# HshNano_v1_0.net
KiCad netlist of a schematic drawn in EAGLE
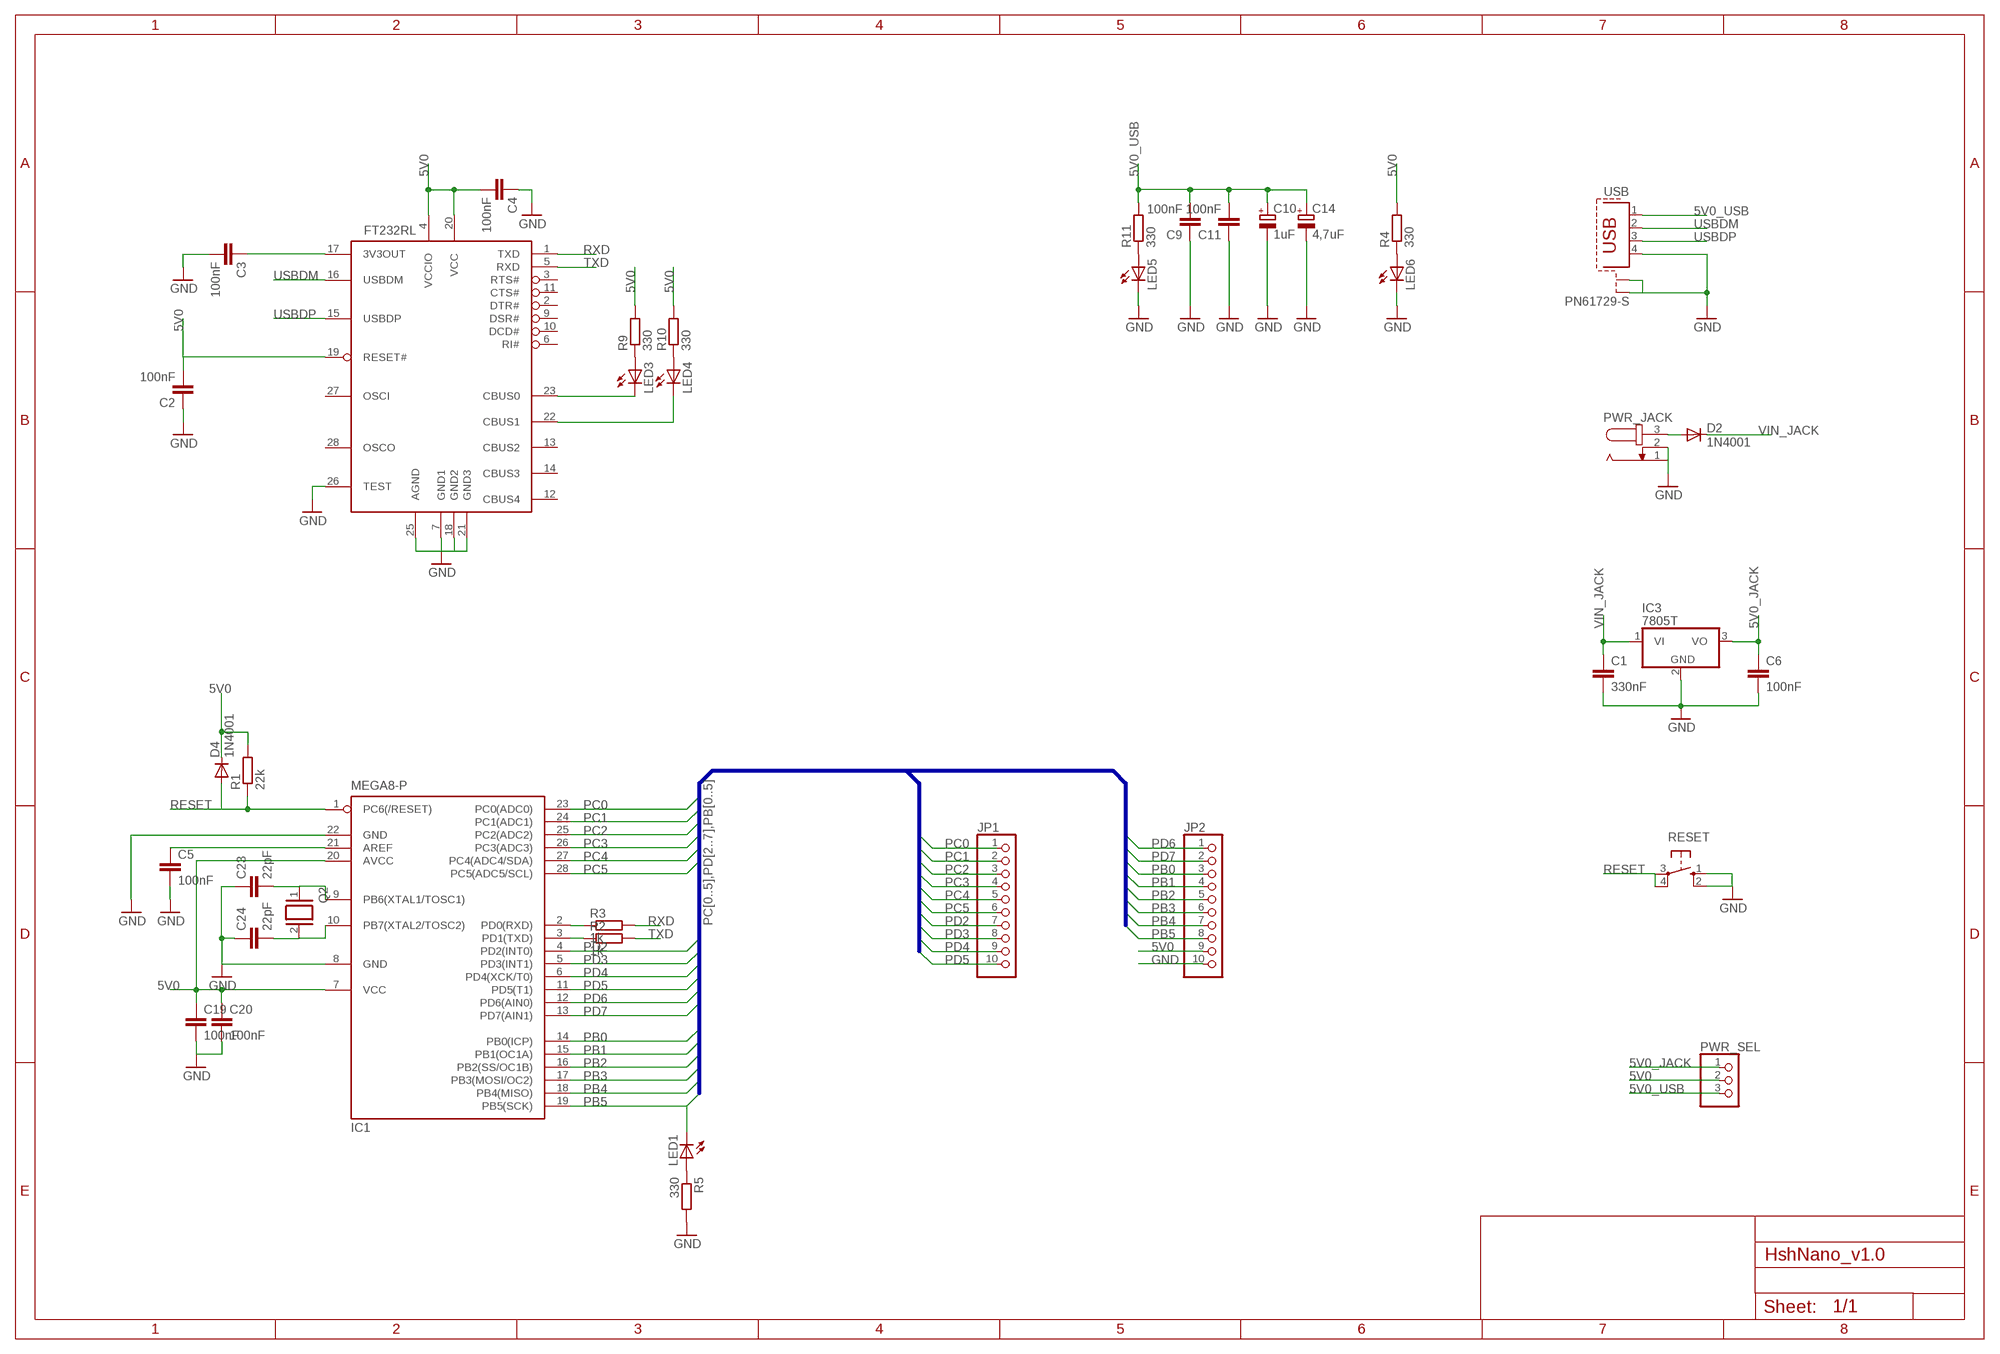
[diagram p0: schematic, sheet 1]

(export (version "E")
  (design (tool "Eeschema 10.0.6"))
  (components
    (comp (ref "C1")
      (value "330nF")
      (footprint "eagle-import:C025-025X050")
      (libsource (lib "eagle-import") (part "C-EU025-025X050"))
    )
    (comp (ref "C2")
      (value "100nF")
      (footprint "eagle-import:C025-025X050")
      (libsource (lib "eagle-import") (part "C-EU025-025X050"))
    )
    (comp (ref "C3")
      (value "100nF")
      (footprint "eagle-import:C025-025X050")
      (libsource (lib "eagle-import") (part "C-EU025-025X050"))
    )
    (comp (ref "C4")
      (value "100nF")
      (footprint "eagle-import:C025-025X050")
      (libsource (lib "eagle-import") (part "C-EU025-025X050"))
    )
    (comp (ref "C5")
      (value "100nF")
      (footprint "eagle-import:C025-025X050")
      (libsource (lib "eagle-import") (part "C-EU025-025X050"))
    )
    (comp (ref "C6")
      (value "100nF")
      (footprint "eagle-import:C025-025X050")
      (libsource (lib "eagle-import") (part "C-EU025-025X050"))
    )
    (comp (ref "C9")
      (value "100nF")
      (footprint "eagle-import:C025-025X050")
      (libsource (lib "eagle-import") (part "C-EU025-025X050"))
    )
    (comp (ref "C10")
      (value "1uF")
      (footprint "eagle-import:E2,5-5")
      (libsource (lib "eagle-import") (part "CPOL-EUE2.5-5"))
    )
    (comp (ref "C11")
      (value "100nF")
      (footprint "eagle-import:C025-025X050")
      (libsource (lib "eagle-import") (part "C-EU025-025X050"))
    )
    (comp (ref "C14")
      (value "4,7uF")
      (footprint "eagle-import:E2,5-5")
      (libsource (lib "eagle-import") (part "CPOL-EUE2.5-5"))
    )
    (comp (ref "C19")
      (value "100nF")
      (footprint "eagle-import:C025-025X050")
      (libsource (lib "eagle-import") (part "C-EU025-025X050"))
    )
    (comp (ref "C20")
      (value "100nF")
      (footprint "eagle-import:C025-025X050")
      (libsource (lib "eagle-import") (part "C-EU025-025X050"))
    )
    (comp (ref "C23")
      (value "22pF")
      (footprint "eagle-import:C025-025X050")
      (libsource (lib "eagle-import") (part "C-EU025-025X050"))
    )
    (comp (ref "C24")
      (value "22pF")
      (footprint "eagle-import:C025-025X050")
      (libsource (lib "eagle-import") (part "C-EU025-025X050"))
    )
    (comp (ref "D2")
      (value "1N4001")
      (footprint "eagle-import:DO41-10")
      (libsource (lib "eagle-import") (part "1N4004"))
    )
    (comp (ref "D4")
      (value "1N4001")
      (footprint "eagle-import:DO41-10")
      (libsource (lib "eagle-import") (part "1N4004"))
    )
    (comp (ref "FT232RL")
      (value "FT232RL")
      (footprint "eagle-import:SSOP28DB")
      (libsource (lib "eagle-import") (part "FT232RL"))
    )
    (comp (ref "IC1")
      (value "MEGA8-P")
      (footprint "eagle-import:DIL28-3")
      (libsource (lib "eagle-import") (part "MEGA8-P"))
    )
    (comp (ref "IC3")
      (value "7805T")
      (footprint "eagle-import:TO220H")
      (libsource (lib "eagle-import") (part "78T05"))
    )
    (comp (ref "JP1")
      (value "PINHD-1X10")
      (footprint "eagle-import:1X10")
      (libsource (lib "eagle-import") (part "PINHD-1X10"))
    )
    (comp (ref "JP2")
      (value "PINHD-1X10")
      (footprint "eagle-import:1X10")
      (libsource (lib "eagle-import") (part "PINHD-1X10"))
    )
    (comp (ref "LED1")
      (value "LED3MM")
      (footprint "eagle-import:LED3MM")
      (libsource (lib "eagle-import") (part "LED3MM"))
    )
    (comp (ref "LED3")
      (value "LED3MM")
      (footprint "eagle-import:LED3MM")
      (libsource (lib "eagle-import") (part "LED3MM"))
    )
    (comp (ref "LED4")
      (value "LED3MM")
      (footprint "eagle-import:LED3MM")
      (libsource (lib "eagle-import") (part "LED3MM"))
    )
    (comp (ref "LED5")
      (value "LED3MM")
      (footprint "eagle-import:LED3MM")
      (libsource (lib "eagle-import") (part "LED3MM"))
    )
    (comp (ref "LED6")
      (value "LED3MM")
      (footprint "eagle-import:LED3MM")
      (libsource (lib "eagle-import") (part "LED3MM"))
    )
    (comp (ref "PWR_JACK")
      (value "JACK-PLUG0")
      (footprint "eagle-import:SPC4077")
      (libsource (lib "eagle-import") (part "JACK-PLUG0"))
    )
    (comp (ref "PWR_SEL")
      (value "PINHD-1X3")
      (footprint "eagle-import:1X03")
      (libsource (lib "eagle-import") (part "PINHD-1X3"))
    )
    (comp (ref "Q2")
      (value "XTAL/S")
      (footprint "eagle-import:QS")
      (libsource (lib "eagle-import") (part "XTAL/S"))
    )
    (comp (ref "R1")
      (value "22k")
      (footprint "eagle-import:0207_10")
      (libsource (lib "eagle-import") (part "R-EU_0207/10"))
    )
    (comp (ref "R2")
      (value "1k")
      (footprint "eagle-import:0207_10")
      (libsource (lib "eagle-import") (part "R-EU_0207/10"))
    )
    (comp (ref "R3")
      (value "1k")
      (footprint "eagle-import:0207_10")
      (libsource (lib "eagle-import") (part "R-EU_0207/10"))
    )
    (comp (ref "R4")
      (value "330")
      (footprint "eagle-import:0207_10")
      (libsource (lib "eagle-import") (part "R-EU_0207/10"))
    )
    (comp (ref "R5")
      (value "330")
      (footprint "eagle-import:0207_10")
      (libsource (lib "eagle-import") (part "R-EU_0207/10"))
    )
    (comp (ref "R9")
      (value "330")
      (footprint "eagle-import:0207_10")
      (libsource (lib "eagle-import") (part "R-EU_0207/10"))
    )
    (comp (ref "R10")
      (value "330")
      (footprint "eagle-import:0207_10")
      (libsource (lib "eagle-import") (part "R-EU_0207/10"))
    )
    (comp (ref "R11")
      (value "330")
      (footprint "eagle-import:0207_10")
      (libsource (lib "eagle-import") (part "R-EU_0207/10"))
    )
    (comp (ref "RESET")
      (value "10-XX")
      (footprint "eagle-import:B3F-10XX")
      (fields (field (name "MPN") "B3F-1000"))
      (libsource (lib "eagle-import") (part "10-XX"))
    )
    (comp (ref "USB")
      (value "PN61729-S")
      (footprint "eagle-import:PN61729-S")
      (fields (field (name "OC_FARNELL") "unknown") (field (name "OC_NEWARK") "unknown"))
      (libsource (lib "eagle-import") (part "PN61729-S"))
    )
  )
  (nets
    (net (code "1") (name "/5V0") (class "Default")
      (node (ref "C19") (pin "1") (pinfunction "1_1") (pintype "passive"))
      (node (ref "C2") (pin "2") (pinfunction "2_2") (pintype "passive"))
      (node (ref "C20") (pin "1") (pinfunction "1_1") (pintype "passive"))
      (node (ref "C4") (pin "2") (pinfunction "2_2") (pintype "passive"))
      (node (ref "D4") (pin "C") (pinfunction "C_C") (pintype "passive"))
      (node (ref "FT232RL") (pin "19") (pinfunction "RESET#_19") (pintype "input"))
      (node (ref "FT232RL") (pin "20") (pinfunction "VCC_20") (pintype "power_in"))
      (node (ref "FT232RL") (pin "4") (pinfunction "VCCIO_4") (pintype "power_in"))
      (node (ref "IC1") (pin "20") (pinfunction "AVCC_20") (pintype "power_in"))
      (node (ref "IC1") (pin "7") (pinfunction "VCC_7") (pintype "power_in"))
      (node (ref "JP2") (pin "9") (pinfunction "9_9") (pintype "passive"))
      (node (ref "PWR_SEL") (pin "2") (pinfunction "2_2") (pintype "passive"))
      (node (ref "R1") (pin "2") (pinfunction "2_2") (pintype "passive"))
      (node (ref "R10") (pin "2") (pinfunction "2_2") (pintype "passive"))
      (node (ref "R4") (pin "2") (pinfunction "2_2") (pintype "passive"))
      (node (ref "R9") (pin "2") (pinfunction "2_2") (pintype "passive"))
    )
    (net (code "2") (name "/5V0_JACK") (class "Default")
      (node (ref "C6") (pin "1") (pinfunction "1_1") (pintype "passive"))
      (node (ref "IC3") (pin "3") (pinfunction "VO_3") (pintype "passive"))
      (node (ref "PWR_SEL") (pin "1") (pinfunction "1_1") (pintype "passive"))
    )
    (net (code "3") (name "/5V0_USB") (class "Default")
      (node (ref "C10") (pin "+") (pinfunction "+_+") (pintype "passive"))
      (node (ref "C11") (pin "2") (pinfunction "2_2") (pintype "passive"))
      (node (ref "C14") (pin "+") (pinfunction "+_+") (pintype "passive"))
      (node (ref "C9") (pin "2") (pinfunction "2_2") (pintype "passive"))
      (node (ref "PWR_SEL") (pin "3") (pinfunction "3_3") (pintype "passive"))
      (node (ref "R11") (pin "2") (pinfunction "2_2") (pintype "passive"))
      (node (ref "USB") (pin "1") (pinfunction "1_1") (pintype "passive"))
    )
    (net (code "4") (name "/PB0") (class "Default")
      (node (ref "IC1") (pin "14") (pinfunction "PB0(ICP)_14") (pintype "bidirectional"))
      (node (ref "JP2") (pin "3") (pinfunction "3_3") (pintype "passive"))
    )
    (net (code "5") (name "/PB1") (class "Default")
      (node (ref "IC1") (pin "15") (pinfunction "PB1(OC1A)_15") (pintype "bidirectional"))
      (node (ref "JP2") (pin "4") (pinfunction "4_4") (pintype "passive"))
    )
    (net (code "6") (name "/PB2") (class "Default")
      (node (ref "IC1") (pin "16") (pinfunction "PB2(SS/OC1B)_16") (pintype "bidirectional"))
      (node (ref "JP2") (pin "5") (pinfunction "5_5") (pintype "passive"))
    )
    (net (code "7") (name "/PB3") (class "Default")
      (node (ref "IC1") (pin "17") (pinfunction "PB3(MOSI/OC2)_17") (pintype "bidirectional"))
      (node (ref "JP2") (pin "6") (pinfunction "6_6") (pintype "passive"))
    )
    (net (code "8") (name "/PB4") (class "Default")
      (node (ref "IC1") (pin "18") (pinfunction "PB4(MISO)_18") (pintype "bidirectional"))
      (node (ref "JP2") (pin "7") (pinfunction "7_7") (pintype "passive"))
    )
    (net (code "9") (name "/PB5") (class "Default")
      (node (ref "IC1") (pin "19") (pinfunction "PB5(SCK)_19") (pintype "bidirectional"))
      (node (ref "JP2") (pin "8") (pinfunction "8_8") (pintype "passive"))
      (node (ref "LED1") (pin "K") (pinfunction "C_K") (pintype "passive"))
    )
    (net (code "10") (name "/PC0") (class "Default")
      (node (ref "IC1") (pin "23") (pinfunction "PC0(ADC0)_23") (pintype "bidirectional"))
      (node (ref "JP1") (pin "1") (pinfunction "1_1") (pintype "passive"))
    )
    (net (code "11") (name "/PC1") (class "Default")
      (node (ref "IC1") (pin "24") (pinfunction "PC1(ADC1)_24") (pintype "bidirectional"))
      (node (ref "JP1") (pin "2") (pinfunction "2_2") (pintype "passive"))
    )
    (net (code "12") (name "/PC2") (class "Default")
      (node (ref "IC1") (pin "25") (pinfunction "PC2(ADC2)_25") (pintype "bidirectional"))
      (node (ref "JP1") (pin "3") (pinfunction "3_3") (pintype "passive"))
    )
    (net (code "13") (name "/PC3") (class "Default")
      (node (ref "IC1") (pin "26") (pinfunction "PC3(ADC3)_26") (pintype "bidirectional"))
      (node (ref "JP1") (pin "4") (pinfunction "4_4") (pintype "passive"))
    )
    (net (code "14") (name "/PC4") (class "Default")
      (node (ref "IC1") (pin "27") (pinfunction "PC4(ADC4/SDA)_27") (pintype "bidirectional"))
      (node (ref "JP1") (pin "5") (pinfunction "5_5") (pintype "passive"))
    )
    (net (code "15") (name "/PC5") (class "Default")
      (node (ref "IC1") (pin "28") (pinfunction "PC5(ADC5/SCL)_28") (pintype "bidirectional"))
      (node (ref "JP1") (pin "6") (pinfunction "6_6") (pintype "passive"))
    )
    (net (code "16") (name "/PD2") (class "Default")
      (node (ref "IC1") (pin "4") (pinfunction "PD2(INT0)_4") (pintype "bidirectional"))
      (node (ref "JP1") (pin "7") (pinfunction "7_7") (pintype "passive"))
    )
    (net (code "17") (name "/PD3") (class "Default")
      (node (ref "IC1") (pin "5") (pinfunction "PD3(INT1)_5") (pintype "bidirectional"))
      (node (ref "JP1") (pin "8") (pinfunction "8_8") (pintype "passive"))
    )
    (net (code "18") (name "/PD4") (class "Default")
      (node (ref "IC1") (pin "6") (pinfunction "PD4(XCK/T0)_6") (pintype "bidirectional"))
      (node (ref "JP1") (pin "9") (pinfunction "9_9") (pintype "passive"))
    )
    (net (code "19") (name "/PD5") (class "Default")
      (node (ref "IC1") (pin "11") (pinfunction "PD5(T1)_11") (pintype "bidirectional"))
      (node (ref "JP1") (pin "10") (pinfunction "10_10") (pintype "passive"))
    )
    (net (code "20") (name "/PD6") (class "Default")
      (node (ref "IC1") (pin "12") (pinfunction "PD6(AIN0)_12") (pintype "bidirectional"))
      (node (ref "JP2") (pin "1") (pinfunction "1_1") (pintype "passive"))
    )
    (net (code "21") (name "/PD7") (class "Default")
      (node (ref "IC1") (pin "13") (pinfunction "PD7(AIN1)_13") (pintype "bidirectional"))
      (node (ref "JP2") (pin "2") (pinfunction "2_2") (pintype "passive"))
    )
    (net (code "22") (name "/RESET") (class "Default")
      (node (ref "D4") (pin "A") (pinfunction "A_A") (pintype "passive"))
      (node (ref "IC1") (pin "1") (pinfunction "PC6(/RESET)_1") (pintype "bidirectional"))
      (node (ref "R1") (pin "1") (pinfunction "1_1") (pintype "passive"))
      (node (ref "RESET") (pin "3") (pinfunction "P_3") (pintype "passive"))
      (node (ref "RESET") (pin "4") (pinfunction "P1_4") (pintype "passive"))
    )
    (net (code "23") (name "/RXD") (class "Default")
      (node (ref "FT232RL") (pin "1") (pinfunction "TXD_1") (pintype "output"))
      (node (ref "R3") (pin "2") (pinfunction "2_2") (pintype "passive"))
    )
    (net (code "24") (name "/TXD") (class "Default")
      (node (ref "FT232RL") (pin "5") (pinfunction "RXD_5") (pintype "input"))
      (node (ref "R2") (pin "2") (pinfunction "2_2") (pintype "passive"))
    )
    (net (code "25") (name "/USBDM") (class "Default")
      (node (ref "FT232RL") (pin "16") (pinfunction "USBDM_16") (pintype "bidirectional"))
      (node (ref "USB") (pin "2") (pinfunction "2_2") (pintype "passive"))
    )
    (net (code "26") (name "/USBDP") (class "Default")
      (node (ref "FT232RL") (pin "15") (pinfunction "USBDP_15") (pintype "bidirectional"))
      (node (ref "USB") (pin "3") (pinfunction "3_3") (pintype "passive"))
    )
    (net (code "27") (name "/VIN_JACK") (class "Default")
      (node (ref "C1") (pin "1") (pinfunction "1_1") (pintype "passive"))
      (node (ref "D2") (pin "C") (pinfunction "C_C") (pintype "passive"))
      (node (ref "IC3") (pin "1") (pinfunction "VI_1") (pintype "input"))
    )
    (net (code "29") (name "GND") (class "Default")
      (node (ref "C1") (pin "2") (pinfunction "2_2") (pintype "passive"))
      (node (ref "C10") (pin "-") (pinfunction "-_-") (pintype "passive"))
      (node (ref "C11") (pin "1") (pinfunction "1_1") (pintype "passive"))
      (node (ref "C14") (pin "-") (pinfunction "-_-") (pintype "passive"))
      (node (ref "C19") (pin "2") (pinfunction "2_2") (pintype "passive"))
      (node (ref "C2") (pin "1") (pinfunction "1_1") (pintype "passive"))
      (node (ref "C20") (pin "2") (pinfunction "2_2") (pintype "passive"))
      (node (ref "C23") (pin "1") (pinfunction "1_1") (pintype "passive"))
      (node (ref "C24") (pin "1") (pinfunction "1_1") (pintype "passive"))
      (node (ref "C3") (pin "2") (pinfunction "2_2") (pintype "passive"))
      (node (ref "C4") (pin "1") (pinfunction "1_1") (pintype "passive"))
      (node (ref "C5") (pin "2") (pinfunction "2_2") (pintype "passive"))
      (node (ref "C6") (pin "2") (pinfunction "2_2") (pintype "passive"))
      (node (ref "C9") (pin "1") (pinfunction "1_1") (pintype "passive"))
      (node (ref "FT232RL") (pin "18") (pinfunction "GND2_18") (pintype "power_in"))
      (node (ref "FT232RL") (pin "21") (pinfunction "GND3_21") (pintype "power_in"))
      (node (ref "FT232RL") (pin "25") (pinfunction "AGND_25") (pintype "power_in"))
      (node (ref "FT232RL") (pin "26") (pinfunction "TEST_26") (pintype "input"))
      (node (ref "FT232RL") (pin "7") (pinfunction "GND1_7") (pintype "power_in"))
      (node (ref "IC1") (pin "22") (pinfunction "GND_22") (pintype "power_in"))
      (node (ref "IC1") (pin "8") (pinfunction "GND_8") (pintype "power_in"))
      (node (ref "IC3") (pin "2") (pinfunction "GND_2") (pintype "passive"))
      (node (ref "JP2") (pin "10") (pinfunction "10_10") (pintype "passive"))
      (node (ref "LED5") (pin "K") (pinfunction "C_K") (pintype "passive"))
      (node (ref "LED6") (pin "K") (pinfunction "C_K") (pintype "passive"))
      (node (ref "PWR_JACK") (pin "1") (pinfunction "1_1") (pintype "passive"))
      (node (ref "PWR_JACK") (pin "2") (pinfunction "2_2") (pintype "passive"))
      (node (ref "R5") (pin "2") (pinfunction "2_2") (pintype "passive"))
      (node (ref "RESET") (pin "1") (pinfunction "S_1") (pintype "passive"))
      (node (ref "RESET") (pin "2") (pinfunction "S1_2") (pintype "passive"))
      (node (ref "USB") (pin "4") (pinfunction "4_4") (pintype "passive"))
      (node (ref "USB") (pin "S1") (pinfunction "S1_S1") (pintype "passive"))
      (node (ref "USB") (pin "S2") (pinfunction "S2_S2") (pintype "passive"))
    )
    (net (code "30") (name "Net-(D2-PadA)") (class "Default")
      (node (ref "D2") (pin "A") (pinfunction "A_A") (pintype "passive"))
      (node (ref "PWR_JACK") (pin "3") (pinfunction "3_3") (pintype "passive"))
    )
    (net (code "31") (name "Net-(FT232RL-3V3OUT)") (class "Default")
      (node (ref "C3") (pin "1") (pinfunction "1_1") (pintype "passive"))
      (node (ref "FT232RL") (pin "17") (pinfunction "3V3OUT_17") (pintype "output"))
    )
    (net (code "32") (name "Net-(FT232RL-CBUS0)") (class "Default")
      (node (ref "FT232RL") (pin "23") (pinfunction "CBUS0_23") (pintype "bidirectional"))
      (node (ref "LED3") (pin "K") (pinfunction "C_K") (pintype "passive"))
    )
    (net (code "33") (name "Net-(FT232RL-CBUS1)") (class "Default")
      (node (ref "FT232RL") (pin "22") (pinfunction "CBUS1_22") (pintype "bidirectional"))
      (node (ref "LED4") (pin "K") (pinfunction "C_K") (pintype "passive"))
    )
    (net (code "34") (name "Net-(IC1-AREF)") (class "Default")
      (node (ref "C5") (pin "1") (pinfunction "1_1") (pintype "passive"))
      (node (ref "IC1") (pin "21") (pinfunction "AREF_21") (pintype "passive"))
    )
    (net (code "35") (name "Net-(IC1-PB6(XTAL1{slash}TOSC1))") (class "Default")
      (node (ref "C23") (pin "2") (pinfunction "2_2") (pintype "passive"))
      (node (ref "IC1") (pin "9") (pinfunction "PB6(XTAL1/TOSC1)_9") (pintype "bidirectional"))
      (node (ref "Q2") (pin "1") (pinfunction "1_1") (pintype "passive"))
    )
    (net (code "36") (name "Net-(IC1-PB7(XTAL2{slash}TOSC2))") (class "Default")
      (node (ref "C24") (pin "2") (pinfunction "2_2") (pintype "passive"))
      (node (ref "IC1") (pin "10") (pinfunction "PB7(XTAL2/TOSC2)_10") (pintype "bidirectional"))
      (node (ref "Q2") (pin "2") (pinfunction "2_2") (pintype "passive"))
    )
    (net (code "37") (name "Net-(IC1-PD0(RXD))") (class "Default")
      (node (ref "IC1") (pin "2") (pinfunction "PD0(RXD)_2") (pintype "bidirectional"))
      (node (ref "R3") (pin "1") (pinfunction "1_1") (pintype "passive"))
    )
    (net (code "38") (name "Net-(IC1-PD1(TXD))") (class "Default")
      (node (ref "IC1") (pin "3") (pinfunction "PD1(TXD)_3") (pintype "bidirectional"))
      (node (ref "R2") (pin "1") (pinfunction "1_1") (pintype "passive"))
    )
    (net (code "39") (name "Net-(LED1-PadA)") (class "Default")
      (node (ref "LED1") (pin "A") (pinfunction "A_A") (pintype "passive"))
      (node (ref "R5") (pin "1") (pinfunction "1_1") (pintype "passive"))
    )
    (net (code "40") (name "Net-(LED3-PadA)") (class "Default")
      (node (ref "LED3") (pin "A") (pinfunction "A_A") (pintype "passive"))
      (node (ref "R9") (pin "1") (pinfunction "1_1") (pintype "passive"))
    )
    (net (code "41") (name "Net-(LED4-PadA)") (class "Default")
      (node (ref "LED4") (pin "A") (pinfunction "A_A") (pintype "passive"))
      (node (ref "R10") (pin "1") (pinfunction "1_1") (pintype "passive"))
    )
    (net (code "42") (name "Net-(LED5-PadA)") (class "Default")
      (node (ref "LED5") (pin "A") (pinfunction "A_A") (pintype "passive"))
      (node (ref "R11") (pin "1") (pinfunction "1_1") (pintype "passive"))
    )
    (net (code "43") (name "Net-(LED6-PadA)") (class "Default")
      (node (ref "LED6") (pin "A") (pinfunction "A_A") (pintype "passive"))
      (node (ref "R4") (pin "1") (pinfunction "1_1") (pintype "passive"))
    )
    (net (code "44") (name "unconnected-(FT232RL-CBUS2-Pad13)") (class "Default")
      (node (ref "FT232RL") (pin "13") (pinfunction "CBUS2_13") (pintype "bidirectional"))
    )
    (net (code "45") (name "unconnected-(FT232RL-CBUS3-Pad14)") (class "Default")
      (node (ref "FT232RL") (pin "14") (pinfunction "CBUS3_14") (pintype "bidirectional"))
    )
    (net (code "46") (name "unconnected-(FT232RL-CBUS4-Pad12)") (class "Default")
      (node (ref "FT232RL") (pin "12") (pinfunction "CBUS4_12") (pintype "bidirectional"))
    )
    (net (code "47") (name "unconnected-(FT232RL-CTS#-Pad11)") (class "Default")
      (node (ref "FT232RL") (pin "11") (pinfunction "CTS#_11") (pintype "input"))
    )
    (net (code "48") (name "unconnected-(FT232RL-DCD#-Pad10)") (class "Default")
      (node (ref "FT232RL") (pin "10") (pinfunction "DCD#_10") (pintype "input"))
    )
    (net (code "49") (name "unconnected-(FT232RL-DSR#-Pad9)") (class "Default")
      (node (ref "FT232RL") (pin "9") (pinfunction "DSR#_9") (pintype "input"))
    )
    (net (code "50") (name "unconnected-(FT232RL-DTR#-Pad2)") (class "Default")
      (node (ref "FT232RL") (pin "2") (pinfunction "DTR#_2") (pintype "output"))
    )
    (net (code "51") (name "unconnected-(FT232RL-OSCI-Pad27)") (class "Default")
      (node (ref "FT232RL") (pin "27") (pinfunction "OSCI_27") (pintype "input"))
    )
    (net (code "52") (name "unconnected-(FT232RL-OSCO-Pad28)") (class "Default")
      (node (ref "FT232RL") (pin "28") (pinfunction "OSCO_28") (pintype "output"))
    )
    (net (code "53") (name "unconnected-(FT232RL-RI#-Pad6)") (class "Default")
      (node (ref "FT232RL") (pin "6") (pinfunction "RI#_6") (pintype "input"))
    )
    (net (code "54") (name "unconnected-(FT232RL-RTS#-Pad3)") (class "Default")
      (node (ref "FT232RL") (pin "3") (pinfunction "RTS#_3") (pintype "output"))
    )
  )
)
